# 03_MCU.net
KiCad netlist of a schematic drawn in Altium Designer
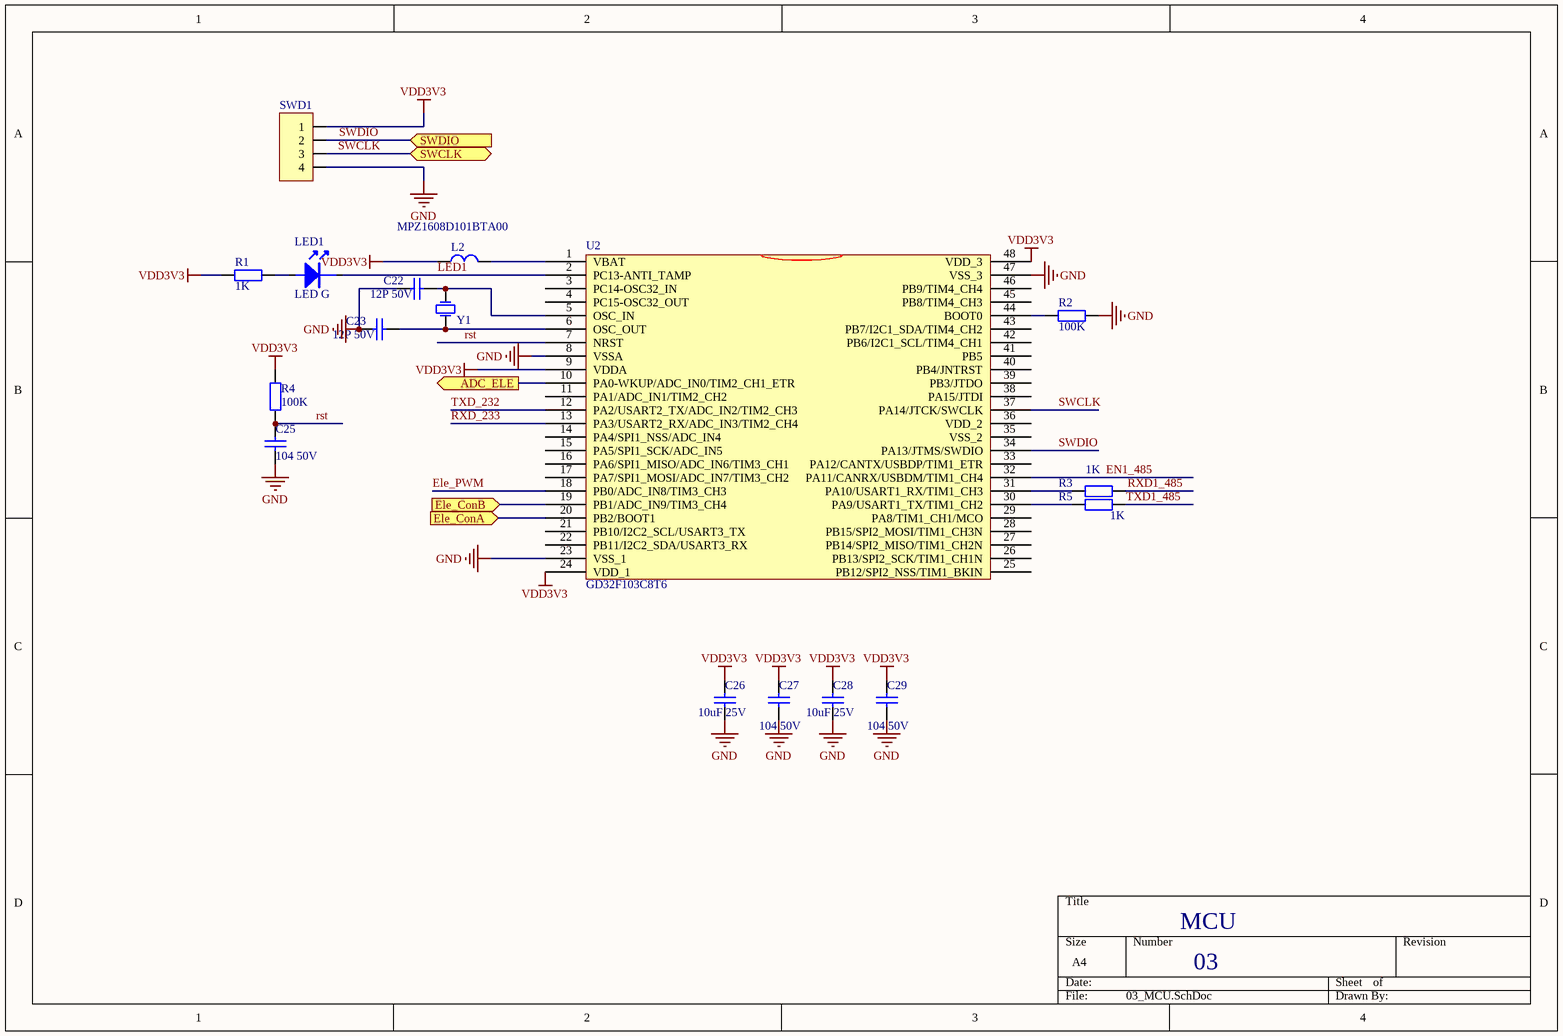
[diagram p0: 03_MCU.SchDoc]

(export (version "E")
  (design (tool "Eeschema 10.0.6"))
  (components
    (comp (ref "C22")
      (value "12P 50V")
      (footprint "SMD-0603C")
      (description "贴片电容 5%")
      (libsource (lib "XiaoyI") (part "CAP4"))
    )
    (comp (ref "C23")
      (value "12P 50V")
      (footprint "SMD-0603C")
      (description "贴片电容 5%")
      (libsource (lib "XiaoyI") (part "CAP4"))
    )
    (comp (ref "C25")
      (value "104 50V")
      (footprint "SMD-0603C")
      (description "贴片电容 20%")
      (libsource (lib "XiaoyI") (part "CAP4"))
    )
    (comp (ref "C26")
      (value "10uF 25V")
      (footprint "SMD-0805C")
      (description "贴片电容 20%")
      (libsource (lib "XiaoyI") (part "CAP4"))
    )
    (comp (ref "C27")
      (value "104 50V")
      (footprint "SMD-0603C")
      (description "贴片电容 20%")
      (libsource (lib "XiaoyI") (part "CAP4"))
    )
    (comp (ref "C28")
      (value "10uF 25V")
      (footprint "SMD-0805C")
      (description "贴片电容 20%")
      (libsource (lib "XiaoyI") (part "CAP4"))
    )
    (comp (ref "C29")
      (value "104 50V")
      (footprint "SMD-0603C")
      (description "贴片电容 20%")
      (libsource (lib "XiaoyI") (part "CAP4"))
    )
    (comp (ref "L2")
      (value "MPZ1608D101BTA00")
      (footprint "SMD-0603")
      (description "磁珠电感 100R 100MHz")
      (libsource (lib "XiaoyI") (part "CIZHU1"))
    )
    (comp (ref "LED1")
      (value "LED G")
      (footprint "SMD-0603D")
      (description "绿色普亮")
      (libsource (lib "ABB") (part "LED"))
    )
    (comp (ref "R1")
      (value "1K")
      (footprint "SMD-0603")
      (description "贴片电阻 5%")
      (libsource (lib "ABB") (part "RES0"))
    )
    (comp (ref "R2")
      (value "100K")
      (footprint "SMD-0603")
      (description "贴片电阻 5%")
      (libsource (lib "") (part "RES2_1"))
    )
    (comp (ref "R3")
      (value "1K")
      (footprint "SMD-0603")
      (description "贴片电阻 5%")
      (libsource (lib "") (part "RES2_1"))
    )
    (comp (ref "R4")
      (value "100K")
      (footprint "SMD-0603")
      (description "贴片电阻 5%")
      (libsource (lib "XiaoyI") (part "RES2"))
    )
    (comp (ref "R5")
      (value "1K")
      (footprint "SMD-0603")
      (description "贴片电阻 5%")
      (libsource (lib "") (part "RES2_1"))
    )
    (comp (ref "SWD1")
      (value "SIP-4 (NC)")
      (footprint "SIP-4")
      (description "ISP 下载")
      (libsource (lib "XiaoyI") (part "SIP-4"))
    )
    (comp (ref "U2")
      (value "GD32F103C8T6")
      (footprint "LQFP48")
      (libsource (lib "stm32") (part "STM32F103C6"))
    )
    (comp (ref "Y1")
      (value "8MHz")
      (footprint "XTAL-3225-2")
      (description "3225 贴片晶振")
      (libsource (lib "XiaoyI") (part "XTAL"))
    )
  )
  (nets
    (net (code "1") (name "/ADC_ELE") (class "Default")
      (node (ref "U2") (pin "10") (pinfunction "PA0-WKUP/ADC_IN0/TIM2_CH1_ETR_10") (pintype "passive"))
    )
    (net (code "2") (name "/EN1_485") (class "Default")
      (node (ref "U2") (pin "32") (pinfunction "PA11/CANRX/USBDM/TIM1_CH4_32") (pintype "passive"))
    )
    (net (code "3") (name "/Ele_ConA") (class "Default")
      (node (ref "U2") (pin "20") (pinfunction "PB2/BOOT1_20") (pintype "passive"))
    )
    (net (code "4") (name "/Ele_ConB") (class "Default")
      (node (ref "U2") (pin "19") (pinfunction "PB1/ADC_IN9/TIM3_CH4_19") (pintype "passive"))
    )
    (net (code "5") (name "/Ele_PWM") (class "Default")
      (node (ref "U2") (pin "18") (pinfunction "PB0/ADC_IN8/TIM3_CH3_18") (pintype "passive"))
    )
    (net (code "6") (name "/LED1") (class "Default")
      (node (ref "LED1") (pin "2") (pinfunction "K_2") (pintype "passive"))
      (node (ref "U2") (pin "2") (pinfunction "PC13-ANTI_TAMP_2") (pintype "passive"))
    )
    (net (code "7") (name "/RXD1_485") (class "Default")
      (node (ref "R3") (pin "2") (pinfunction "2_2") (pintype "passive"))
    )
    (net (code "8") (name "/RXD_233") (class "Default")
      (node (ref "U2") (pin "13") (pinfunction "PA3/USART2_RX/ADC_IN3/TIM2_CH4_13") (pintype "passive"))
    )
    (net (code "9") (name "/SWCLK") (class "Default")
      (node (ref "SWD1") (pin "3") (pinfunction "3_3") (pintype "passive"))
      (node (ref "U2") (pin "37") (pinfunction "PA14/JTCK/SWCLK_37") (pintype "passive"))
    )
    (net (code "10") (name "/SWDIO") (class "Default")
      (node (ref "SWD1") (pin "2") (pinfunction "2_2") (pintype "passive"))
      (node (ref "U2") (pin "34") (pinfunction "PA13/JTMS/SWDIO_34") (pintype "passive"))
    )
    (net (code "11") (name "/TXD1_485") (class "Default")
      (node (ref "R5") (pin "2") (pinfunction "2_2") (pintype "passive"))
    )
    (net (code "12") (name "/TXD_232") (class "Default")
      (node (ref "U2") (pin "12") (pinfunction "PA2/USART2_TX/ADC_IN2/TIM2_CH3_12") (pintype "passive"))
    )
    (net (code "13") (name "/rst") (class "Default")
      (node (ref "C25") (pin "2") (pinfunction "2_2") (pintype "passive"))
      (node (ref "R4") (pin "2") (pinfunction "2_2") (pintype "passive"))
      (node (ref "U2") (pin "7") (pinfunction "NRST_7") (pintype "passive"))
    )
    (net (code "14") (name "GND") (class "Default")
      (node (ref "C22") (pin "2") (pinfunction "2_2") (pintype "passive"))
      (node (ref "C23") (pin "2") (pinfunction "2_2") (pintype "passive"))
      (node (ref "C25") (pin "1") (pinfunction "1_1") (pintype "passive"))
      (node (ref "C26") (pin "1") (pinfunction "1_1") (pintype "passive"))
      (node (ref "C27") (pin "1") (pinfunction "1_1") (pintype "passive"))
      (node (ref "C28") (pin "1") (pinfunction "1_1") (pintype "passive"))
      (node (ref "C29") (pin "1") (pinfunction "1_1") (pintype "passive"))
      (node (ref "R2") (pin "2") (pinfunction "2_2") (pintype "passive"))
      (node (ref "SWD1") (pin "4") (pinfunction "4_4") (pintype "passive"))
      (node (ref "U2") (pin "23") (pinfunction "VSS_1_23") (pintype "passive"))
      (node (ref "U2") (pin "47") (pinfunction "VSS_3_47") (pintype "passive"))
      (node (ref "U2") (pin "8") (pinfunction "VSSA_8") (pintype "passive"))
    )
    (net (code "15") (name "Net-(LED1-A)") (class "Default")
      (node (ref "LED1") (pin "1") (pinfunction "A_1") (pintype "passive"))
      (node (ref "R1") (pin "1") (pinfunction "1_1") (pintype "passive"))
    )
    (net (code "16") (name "Net-(U2-BOOT0)") (class "Default")
      (node (ref "R2") (pin "1") (pinfunction "1_1") (pintype "passive"))
      (node (ref "U2") (pin "44") (pinfunction "BOOT0_44") (pintype "passive"))
    )
    (net (code "17") (name "Net-(U2-OSC_IN)") (class "Default")
      (node (ref "C22") (pin "1") (pinfunction "1_1") (pintype "passive"))
      (node (ref "U2") (pin "5") (pinfunction "OSC_IN_5") (pintype "passive"))
      (node (ref "Y1") (pin "1") (pinfunction "OSC1_1") (pintype "passive"))
    )
    (net (code "18") (name "Net-(U2-OSC_OUT)") (class "Default")
      (node (ref "C23") (pin "1") (pinfunction "1_1") (pintype "passive"))
      (node (ref "U2") (pin "6") (pinfunction "OSC_OUT_6") (pintype "passive"))
      (node (ref "Y1") (pin "2") (pinfunction "OSC2_2") (pintype "passive"))
    )
    (net (code "19") (name "Net-(U2-PA9{slash}USART1_TX{slash}TIM1_CH2)") (class "Default")
      (node (ref "R5") (pin "1") (pinfunction "1_1") (pintype "passive"))
      (node (ref "U2") (pin "30") (pinfunction "PA9/USART1_TX/TIM1_CH2_30") (pintype "passive"))
    )
    (net (code "20") (name "Net-(U2-PA10{slash}USART1_RX{slash}TIM1_CH3)") (class "Default")
      (node (ref "R3") (pin "1") (pinfunction "1_1") (pintype "passive"))
      (node (ref "U2") (pin "31") (pinfunction "PA10/USART1_RX/TIM1_CH3_31") (pintype "passive"))
    )
    (net (code "21") (name "Net-(U2-VBAT)") (class "Default")
      (node (ref "L2") (pin "1") (pinfunction "1_1") (pintype "passive"))
      (node (ref "U2") (pin "1") (pinfunction "VBAT_1") (pintype "passive"))
    )
    (net (code "22") (name "VDD3V3") (class "Default")
      (node (ref "C26") (pin "2") (pinfunction "2_2") (pintype "passive"))
      (node (ref "C27") (pin "2") (pinfunction "2_2") (pintype "passive"))
      (node (ref "C28") (pin "2") (pinfunction "2_2") (pintype "passive"))
      (node (ref "C29") (pin "2") (pinfunction "2_2") (pintype "passive"))
      (node (ref "L2") (pin "2") (pinfunction "2_2") (pintype "passive"))
      (node (ref "R1") (pin "2") (pinfunction "2_2") (pintype "passive"))
      (node (ref "R4") (pin "1") (pinfunction "1_1") (pintype "passive"))
      (node (ref "SWD1") (pin "1") (pinfunction "1_1") (pintype "passive"))
      (node (ref "U2") (pin "24") (pinfunction "VDD_1_24") (pintype "passive"))
      (node (ref "U2") (pin "48") (pinfunction "VDD_3_48") (pintype "passive"))
      (node (ref "U2") (pin "9") (pinfunction "VDDA_9") (pintype "passive"))
    )
    (net (code "23") (name "unconnected-(U2-PA1{slash}ADC_IN1{slash}TIM2_CH2-Pad11)") (class "Default")
      (node (ref "U2") (pin "11") (pinfunction "PA1/ADC_IN1/TIM2_CH2_11") (pintype "passive"))
    )
    (net (code "24") (name "unconnected-(U2-PA4{slash}SPI1_NSS{slash}ADC_IN4-Pad14)") (class "Default")
      (node (ref "U2") (pin "14") (pinfunction "PA4/SPI1_NSS/ADC_IN4_14") (pintype "passive"))
    )
    (net (code "25") (name "unconnected-(U2-PA5{slash}SPI1_SCK{slash}ADC_IN5-Pad15)") (class "Default")
      (node (ref "U2") (pin "15") (pinfunction "PA5/SPI1_SCK/ADC_IN5_15") (pintype "passive"))
    )
    (net (code "26") (name "unconnected-(U2-PA6{slash}SPI1_MISO{slash}ADC_IN6{slash}TIM3_CH1-Pad16)") (class "Default")
      (node (ref "U2") (pin "16") (pinfunction "PA6/SPI1_MISO/ADC_IN6/TIM3_CH1_16") (pintype "passive"))
    )
    (net (code "27") (name "unconnected-(U2-PA7{slash}SPI1_MOSI{slash}ADC_IN7{slash}TIM3_CH2-Pad17)") (class "Default")
      (node (ref "U2") (pin "17") (pinfunction "PA7/SPI1_MOSI/ADC_IN7/TIM3_CH2_17") (pintype "passive"))
    )
    (net (code "28") (name "unconnected-(U2-PA8{slash}TIM1_CH1{slash}MCO-Pad29)") (class "Default")
      (node (ref "U2") (pin "29") (pinfunction "PA8/TIM1_CH1/MCO_29") (pintype "passive"))
    )
    (net (code "29") (name "unconnected-(U2-PA12{slash}CANTX{slash}USBDP{slash}TIM1_ETR-Pad33)") (class "Default")
      (node (ref "U2") (pin "33") (pinfunction "PA12/CANTX/USBDP/TIM1_ETR_33") (pintype "passive"))
    )
    (net (code "30") (name "unconnected-(U2-PA15{slash}JTDI-Pad38)") (class "Default")
      (node (ref "U2") (pin "38") (pinfunction "PA15/JTDI_38") (pintype "passive"))
    )
    (net (code "31") (name "unconnected-(U2-PB3{slash}JTDO-Pad39)") (class "Default")
      (node (ref "U2") (pin "39") (pinfunction "PB3/JTDO_39") (pintype "passive"))
    )
    (net (code "32") (name "unconnected-(U2-PB4{slash}JNTRST-Pad40)") (class "Default")
      (node (ref "U2") (pin "40") (pinfunction "PB4/JNTRST_40") (pintype "passive"))
    )
    (net (code "33") (name "unconnected-(U2-PB5-Pad41)") (class "Default")
      (node (ref "U2") (pin "41") (pinfunction "PB5_41") (pintype "passive"))
    )
    (net (code "34") (name "unconnected-(U2-PB6{slash}I2C1_SCL{slash}TIM4_CH1-Pad42)") (class "Default")
      (node (ref "U2") (pin "42") (pinfunction "PB6/I2C1_SCL/TIM4_CH1_42") (pintype "passive"))
    )
    (net (code "35") (name "unconnected-(U2-PB7{slash}I2C1_SDA{slash}TIM4_CH2-Pad43)") (class "Default")
      (node (ref "U2") (pin "43") (pinfunction "PB7/I2C1_SDA/TIM4_CH2_43") (pintype "passive"))
    )
    (net (code "36") (name "unconnected-(U2-PB8{slash}TIM4_CH3-Pad45)") (class "Default")
      (node (ref "U2") (pin "45") (pinfunction "PB8/TIM4_CH3_45") (pintype "passive"))
    )
    (net (code "37") (name "unconnected-(U2-PB9{slash}TIM4_CH4-Pad46)") (class "Default")
      (node (ref "U2") (pin "46") (pinfunction "PB9/TIM4_CH4_46") (pintype "passive"))
    )
    (net (code "38") (name "unconnected-(U2-PB10{slash}I2C2_SCL{slash}USART3_TX-Pad21)") (class "Default")
      (node (ref "U2") (pin "21") (pinfunction "PB10/I2C2_SCL/USART3_TX_21") (pintype "passive"))
    )
    (net (code "39") (name "unconnected-(U2-PB11{slash}I2C2_SDA{slash}USART3_RX-Pad22)") (class "Default")
      (node (ref "U2") (pin "22") (pinfunction "PB11/I2C2_SDA/USART3_RX_22") (pintype "passive"))
    )
    (net (code "40") (name "unconnected-(U2-PB12{slash}SPI2_NSS{slash}TIM1_BKIN-Pad25)") (class "Default")
      (node (ref "U2") (pin "25") (pinfunction "PB12/SPI2_NSS/TIM1_BKIN_25") (pintype "passive"))
    )
    (net (code "41") (name "unconnected-(U2-PB13{slash}SPI2_SCK{slash}TIM1_CH1N-Pad26)") (class "Default")
      (node (ref "U2") (pin "26") (pinfunction "PB13/SPI2_SCK/TIM1_CH1N_26") (pintype "passive"))
    )
    (net (code "42") (name "unconnected-(U2-PB14{slash}SPI2_MISO{slash}TIM1_CH2N-Pad27)") (class "Default")
      (node (ref "U2") (pin "27") (pinfunction "PB14/SPI2_MISO/TIM1_CH2N_27") (pintype "passive"))
    )
    (net (code "43") (name "unconnected-(U2-PB15{slash}SPI2_MOSI{slash}TIM1_CH3N-Pad28)") (class "Default")
      (node (ref "U2") (pin "28") (pinfunction "PB15/SPI2_MOSI/TIM1_CH3N_28") (pintype "passive"))
    )
    (net (code "44") (name "unconnected-(U2-PC14-OSC32_IN-Pad3)") (class "Default")
      (node (ref "U2") (pin "3") (pinfunction "PC14-OSC32_IN_3") (pintype "passive"))
    )
    (net (code "45") (name "unconnected-(U2-PC15-OSC32_OUT-Pad4)") (class "Default")
      (node (ref "U2") (pin "4") (pinfunction "PC15-OSC32_OUT_4") (pintype "passive"))
    )
    (net (code "46") (name "unconnected-(U2-VDD_2-Pad36)") (class "Default")
      (node (ref "U2") (pin "36") (pinfunction "VDD_2_36") (pintype "passive"))
    )
    (net (code "47") (name "unconnected-(U2-VSS_2-Pad35)") (class "Default")
      (node (ref "U2") (pin "35") (pinfunction "VSS_2_35") (pintype "passive"))
    )
  )
)
